# 3yp_node.net
KiCad netlist of a schematic drawn in EAGLE
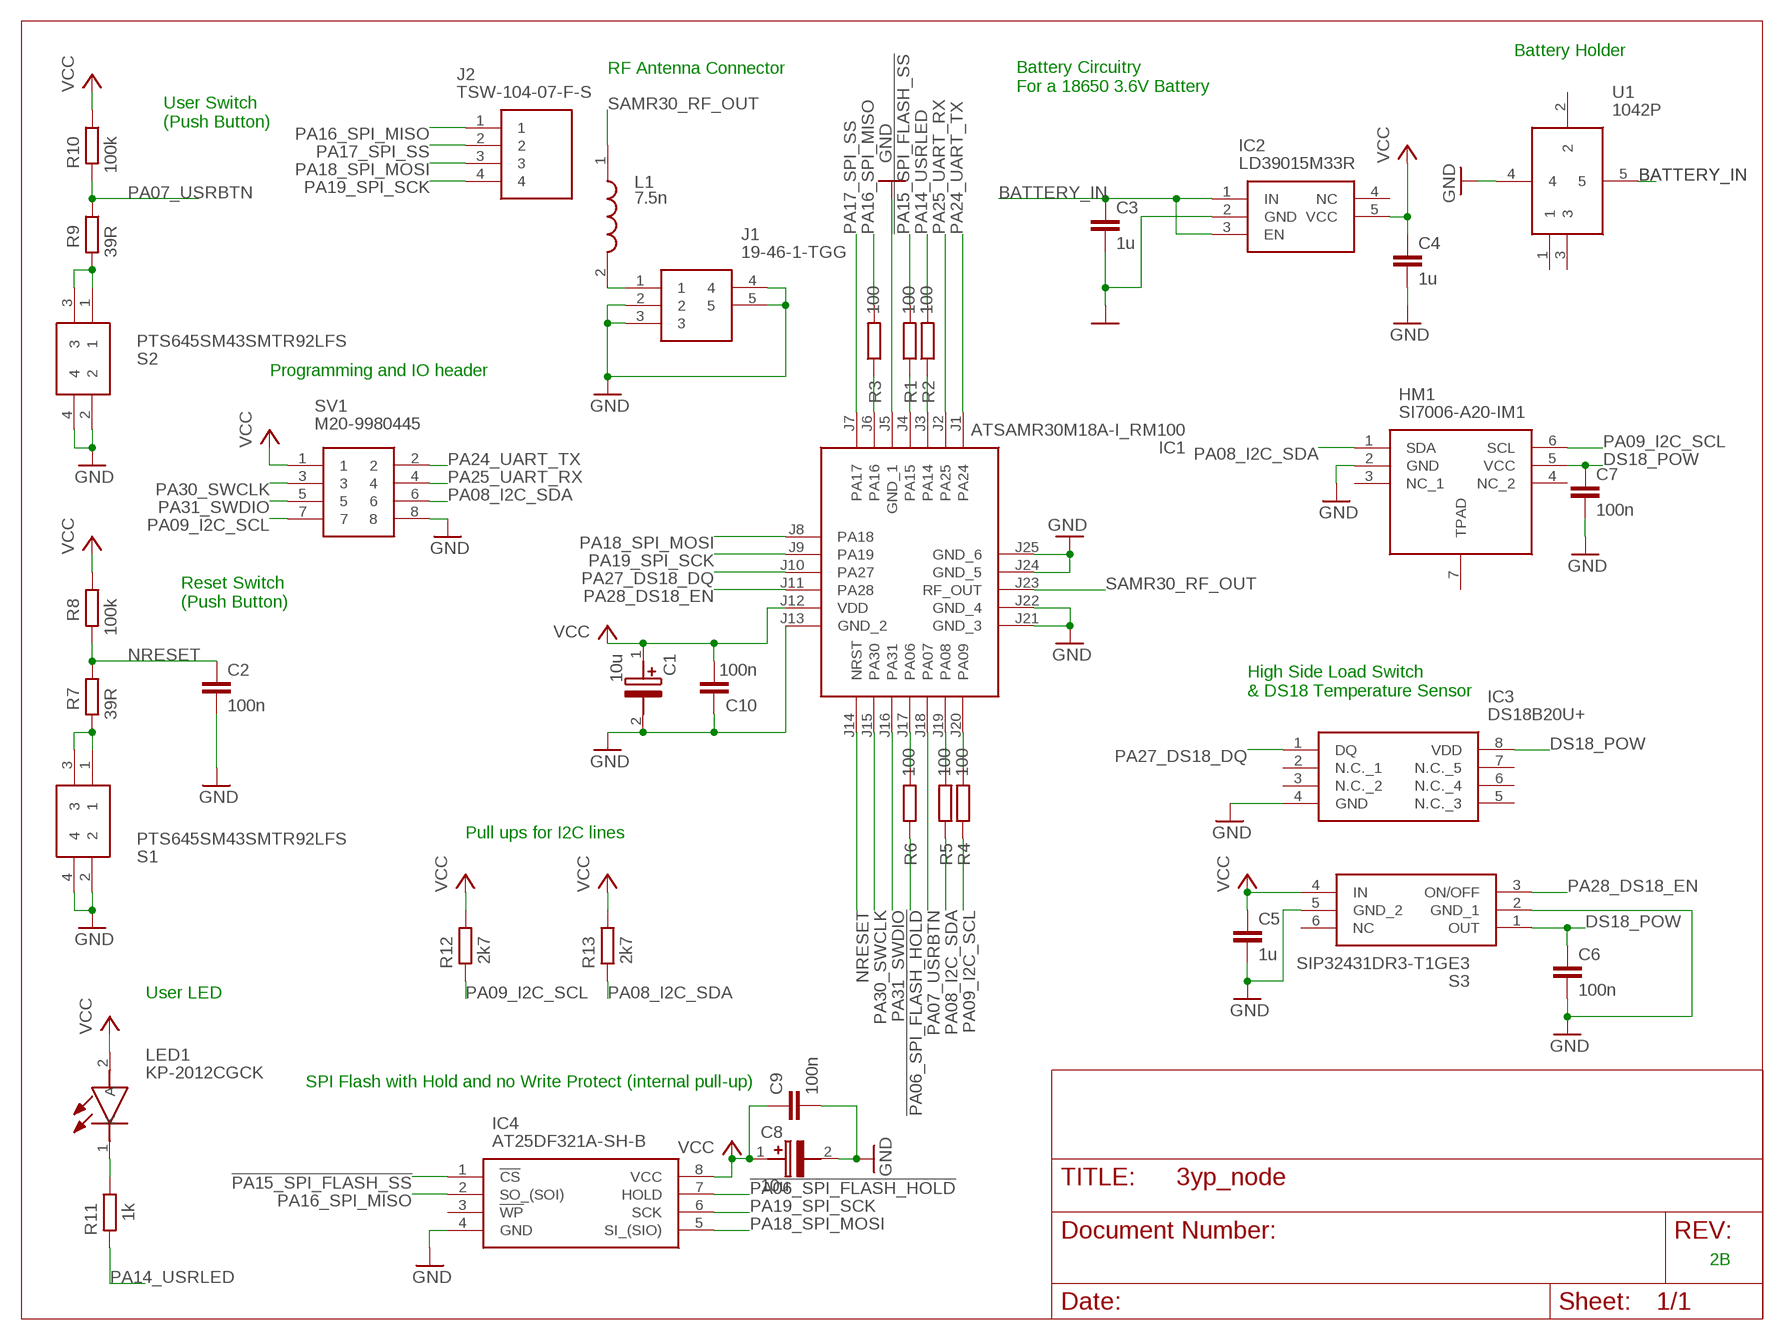
[diagram p0: schematic, sheet 1]

(export (version "E")
  (design (tool "Eeschema 10.0.6"))
  (components
    (comp (ref "C1")
      (value "10u")
      (footprint "eagle-import:CAPPM2014X170N")
      (fields
        (field (name "MANUFACTURER_PART_NUMBER") "TAJP106K006RNJ")
        (field (name "MOUSER_PART_NUMBER") "581-TAJP106K006RNJ")
      )
      (libsource (lib "eagle-import") (part "TAJP106K006RNJ"))
    )
    (comp (ref "C2")
      (value "100n")
      (footprint "eagle-import:C0805")
      (libsource (lib "eagle-import") (part "C-EUC0805"))
    )
    (comp (ref "C3")
      (value "1u")
      (footprint "eagle-import:C0805")
      (libsource (lib "eagle-import") (part "C-EUC0805"))
    )
    (comp (ref "C4")
      (value "1u")
      (footprint "eagle-import:C0805")
      (libsource (lib "eagle-import") (part "C-EUC0805"))
    )
    (comp (ref "C5")
      (value "1u")
      (footprint "eagle-import:C0805")
      (libsource (lib "eagle-import") (part "C-EUC0805"))
    )
    (comp (ref "C6")
      (value "100n")
      (footprint "eagle-import:C0805")
      (libsource (lib "eagle-import") (part "C-EUC0805"))
    )
    (comp (ref "C7")
      (value "100n")
      (footprint "eagle-import:C0805")
      (libsource (lib "eagle-import") (part "C-EUC0805"))
    )
    (comp (ref "C8")
      (value "10u")
      (footprint "eagle-import:CAPPM2014X170N")
      (fields
        (field (name "MANUFACTURER_PART_NUMBER") "TAJP106K006RNJ")
        (field (name "MOUSER_PART_NUMBER") "581-TAJP106K006RNJ")
      )
      (libsource (lib "eagle-import") (part "TAJP106K006RNJ"))
    )
    (comp (ref "C9")
      (value "100n")
      (footprint "eagle-import:C0805")
      (libsource (lib "eagle-import") (part "C-EUC0805"))
    )
    (comp (ref "C10")
      (value "100n")
      (footprint "eagle-import:C0805")
      (libsource (lib "eagle-import") (part "C-EUC0805"))
    )
    (comp (ref "HM1")
      (value "SI7006-A20-IM1")
      (footprint "eagle-import:SON100P300X300X80-7N")
      (fields
        (field (name "MANUFACTURER_PART_NUMBER") "Si7006-A20-IM1")
        (field (name "MOUSER_PART_NUMBER") "634-SI7006-A20-IM1")
        (field (name "RS_PART_NUMBER") "8652283P")
      )
      (libsource (lib "eagle-import") (part "SI7006-A20-IM1"))
    )
    (comp (ref "IC1")
      (value "ATSAMR30M18A-I_RM100")
      (footprint "eagle-import:ATSAMR30M18AIRM100")
      (fields
        (field (name "MANUFACTURER_PART_NUMBER") "ATSAMR30M18A-I/RM100")
        (field (name "MOUSER_PART_NUMBER") "556-AMR30M18AIRM100")
        (field (name "RS_PART_NUMBER") "1840450")
      )
      (libsource (lib "eagle-import") (part "ATSAMR30M18A-I_RM100"))
    )
    (comp (ref "IC2")
      (value "LD39015M33R")
      (footprint "eagle-import:SOT95P280X145-5N")
      (fields
        (field (name "MOUSER_PART_NUMBER") "511-LD39015M33R")
        (field (name "RS_PART_NUMBER") "7958965P")
      )
      (libsource (lib "eagle-import") (part "LD39015M33R"))
    )
    (comp (ref "IC3")
      (value "DS18B20U+")
      (footprint "eagle-import:SOP65P490X110-8N")
      (fields (field (name "MOUSER_PART_NUMBER") "700-DS18B20U"))
      (libsource (lib "eagle-import") (part "DS18B20U+"))
    )
    (comp (ref "IC4")
      (value "AT25DF321A-SH-B")
      (footprint "eagle-import:SOIC127P798X216-8N")
      (fields (field (name "MOUSER_PART_NUMBER") "556-AT25DF321A-SH-B"))
      (libsource (lib "eagle-import") (part "AT25DF321A-SH-B"))
    )
    (comp (ref "J1")
      (value "19-46-1-TGG")
      (footprint "eagle-import:19-46-1-TGG_1")
      (libsource (lib "eagle-import") (part "19-46-1-TGG"))
    )
    (comp (ref "J2")
      (value "TSW-104-07-F-S")
      (footprint "eagle-import:HDRV4W64P254_1X4_1016X241X838P")
      (fields (field (name "MOUSER_PART_NUMBER") "200-TSW10407FS") (field (name "RS_PART_NUMBER") "1612530"))
      (libsource (lib "eagle-import") (part "TSW-104-07-F-S"))
    )
    (comp (ref "L1")
      (value "7.5n")
      (footprint "eagle-import:INDC1006X60N")
      (fields
        (field (name "MANUFACTURER_PART_NUMBER") "MHQ1005P10NJT")
        (field (name "MOUSER_PART_NUMBER") "810-MHQ1005P10NJT")
        (field (name "RS_PART_NUMBER") "7958243P")
      )
      (libsource (lib "eagle-import") (part "MHQ1005P10NJT"))
    )
    (comp (ref "LED1")
      (value "KP-2012CGCK")
      (footprint "eagle-import:LEDC2012X110N")
      (fields (field (name "RS_PART_NUMBER") "8610037P"))
      (libsource (lib "eagle-import") (part "KP-2012CGCK"))
    )
    (comp (ref "R1")
      (value "100")
      (footprint "eagle-import:R0603")
      (libsource (lib "eagle-import") (part "R-EU_R0603"))
    )
    (comp (ref "R2")
      (value "100")
      (footprint "eagle-import:R0603")
      (libsource (lib "eagle-import") (part "R-EU_R0603"))
    )
    (comp (ref "R3")
      (value "100")
      (footprint "eagle-import:R0603")
      (libsource (lib "eagle-import") (part "R-EU_R0603"))
    )
    (comp (ref "R4")
      (value "100")
      (footprint "eagle-import:R0603")
      (libsource (lib "eagle-import") (part "R-EU_R0603"))
    )
    (comp (ref "R5")
      (value "100")
      (footprint "eagle-import:R0603")
      (libsource (lib "eagle-import") (part "R-EU_R0603"))
    )
    (comp (ref "R6")
      (value "100")
      (footprint "eagle-import:R0603")
      (libsource (lib "eagle-import") (part "R-EU_R0603"))
    )
    (comp (ref "R7")
      (value "39R")
      (footprint "eagle-import:R0603")
      (libsource (lib "eagle-import") (part "R-EU_R0603"))
    )
    (comp (ref "R8")
      (value "100k")
      (footprint "eagle-import:R0603")
      (libsource (lib "eagle-import") (part "R-EU_R0603"))
    )
    (comp (ref "R9")
      (value "39R")
      (footprint "eagle-import:R0603")
      (libsource (lib "eagle-import") (part "R-EU_R0603"))
    )
    (comp (ref "R10")
      (value "100k")
      (footprint "eagle-import:R0603")
      (libsource (lib "eagle-import") (part "R-EU_R0603"))
    )
    (comp (ref "R11")
      (value "1k")
      (footprint "eagle-import:R0603")
      (libsource (lib "eagle-import") (part "R-EU_R0603"))
    )
    (comp (ref "R12")
      (value "2k7")
      (footprint "eagle-import:R0603")
      (libsource (lib "eagle-import") (part "R-EU_R0603"))
    )
    (comp (ref "R13")
      (value "2k7")
      (footprint "eagle-import:R0603")
      (libsource (lib "eagle-import") (part "R-EU_R0603"))
    )
    (comp (ref "S1")
      (value "PTS645SM43SMTR92LFS")
      (footprint "eagle-import:PTS645(SMT)")
      (fields (field (name "MOUSER_PART_NUMBER") "611-PTS645SM43SMTR92"))
      (libsource (lib "eagle-import") (part "PTS645SM43SMTR92LFS"))
    )
    (comp (ref "S2")
      (value "PTS645SM43SMTR92LFS")
      (footprint "eagle-import:PTS645(SMT)")
      (fields (field (name "MOUSER_PART_NUMBER") "611-PTS645SM43SMTR92"))
      (libsource (lib "eagle-import") (part "PTS645SM43SMTR92LFS"))
    )
    (comp (ref "S3")
      (value "SIP32431DR3-T1GE3")
      (footprint "eagle-import:SOT65P210X110-6N")
      (fields
        (field (name "MOUSER_PART_NUMBER") "781-SIP32431DR3-GE3")
        (field (name "RS_PART_NUMBER") "1807353")
      )
      (libsource (lib "eagle-import") (part "SIP32431DR3-T1GE3"))
    )
    (comp (ref "SV1")
      (value "M20-9980445")
      (footprint "eagle-import:HDRV8W64P254_2X4_1016X508X868P")
      (fields
        (field (name "MOUSER_PART_NUMBER") "855-M20-9980445")
        (field (name "RS_PART_NUMBER") "6812941P")
      )
      (libsource (lib "eagle-import") (part "M20-9980445"))
    )
    (comp (ref "U1")
      (value "1042P")
      (footprint "eagle-import:1042P")
      (fields (field (name "MOUSER_PART_NUMBER") "534-1042P"))
      (libsource (lib "eagle-import") (part "1042P"))
    )
  )
  (nets
    (net (code "1") (name "/BATTERY_IN") (class "Default")
      (node (ref "C3") (pin "1") (pinfunction "1_1") (pintype "passive"))
      (node (ref "IC2") (pin "1") (pinfunction "IN_1") (pintype "input"))
      (node (ref "IC2") (pin "3") (pinfunction "EN_3") (pintype "bidirectional"))
      (node (ref "U1") (pin "5") (pinfunction "5_5") (pintype "bidirectional"))
    )
    (net (code "2") (name "/DS18_POW") (class "Default")
      (node (ref "C6") (pin "1") (pinfunction "1_1") (pintype "passive"))
      (node (ref "C7") (pin "1") (pinfunction "1_1") (pintype "passive"))
      (node (ref "HM1") (pin "5") (pinfunction "VCC_5") (pintype "power_in"))
      (node (ref "IC3") (pin "8") (pinfunction "VDD_8") (pintype "power_in"))
      (node (ref "S3") (pin "1") (pinfunction "OUT_1") (pintype "power_in"))
    )
    (net (code "3") (name "/NRESET") (class "Default")
      (node (ref "C2") (pin "1") (pinfunction "1_1") (pintype "passive"))
      (node (ref "IC1") (pin "J14") (pinfunction "NRST_J14") (pintype "bidirectional"))
      (node (ref "R7") (pin "1") (pinfunction "1_1") (pintype "passive"))
      (node (ref "R8") (pin "2") (pinfunction "2_2") (pintype "passive"))
    )
    (net (code "4") (name "/PA07_USRBTN") (class "Default")
      (node (ref "IC1") (pin "J18") (pinfunction "PA07_J18") (pintype "bidirectional"))
      (node (ref "R10") (pin "2") (pinfunction "2_2") (pintype "passive"))
      (node (ref "R9") (pin "1") (pinfunction "1_1") (pintype "passive"))
    )
    (net (code "5") (name "/PA08_I2C_SDA") (class "Default")
      (node (ref "HM1") (pin "1") (pinfunction "SDA_1") (pintype "bidirectional"))
      (node (ref "R13") (pin "2") (pinfunction "2_2") (pintype "passive"))
      (node (ref "R5") (pin "1") (pinfunction "1_1") (pintype "passive"))
      (node (ref "SV1") (pin "6") (pinfunction "6_6") (pintype "bidirectional"))
    )
    (net (code "6") (name "/PA09_I2C_SCL") (class "Default")
      (node (ref "HM1") (pin "6") (pinfunction "SCL_6") (pintype "input"))
      (node (ref "R12") (pin "2") (pinfunction "2_2") (pintype "passive"))
      (node (ref "R4") (pin "1") (pinfunction "1_1") (pintype "passive"))
      (node (ref "SV1") (pin "7") (pinfunction "7_7") (pintype "bidirectional"))
    )
    (net (code "7") (name "/PA14_USRLED") (class "Default")
      (node (ref "R11") (pin "2") (pinfunction "2_2") (pintype "passive"))
      (node (ref "R2") (pin "2") (pinfunction "2_2") (pintype "passive"))
    )
    (net (code "8") (name "/PA16_SPI_MISO") (class "Default")
      (node (ref "IC4") (pin "2") (pinfunction "SO_(SOI)_2") (pintype "bidirectional"))
      (node (ref "J2") (pin "1") (pinfunction "1_1") (pintype "bidirectional"))
      (node (ref "R3") (pin "2") (pinfunction "2_2") (pintype "passive"))
    )
    (net (code "9") (name "/PA17_SPI_SS") (class "Default")
      (node (ref "IC1") (pin "J7") (pinfunction "PA17_J7") (pintype "bidirectional"))
      (node (ref "J2") (pin "2") (pinfunction "2_2") (pintype "bidirectional"))
    )
    (net (code "10") (name "/PA18_SPI_MOSI") (class "Default")
      (node (ref "IC1") (pin "J8") (pinfunction "PA18_J8") (pintype "bidirectional"))
      (node (ref "IC4") (pin "5") (pinfunction "SI_(SIO)_5") (pintype "bidirectional"))
      (node (ref "J2") (pin "3") (pinfunction "3_3") (pintype "bidirectional"))
    )
    (net (code "11") (name "/PA19_SPI_SCK") (class "Default")
      (node (ref "IC1") (pin "J9") (pinfunction "PA19_J9") (pintype "bidirectional"))
      (node (ref "IC4") (pin "6") (pinfunction "SCK_6") (pintype "bidirectional"))
      (node (ref "J2") (pin "4") (pinfunction "4_4") (pintype "bidirectional"))
    )
    (net (code "12") (name "/PA24_UART_TX") (class "Default")
      (node (ref "IC1") (pin "J1") (pinfunction "PA24_J1") (pintype "bidirectional"))
      (node (ref "SV1") (pin "2") (pinfunction "2_2") (pintype "bidirectional"))
    )
    (net (code "13") (name "/PA25_UART_RX") (class "Default")
      (node (ref "IC1") (pin "J2") (pinfunction "PA25_J2") (pintype "bidirectional"))
      (node (ref "SV1") (pin "4") (pinfunction "4_4") (pintype "bidirectional"))
    )
    (net (code "14") (name "/PA27_DS18_DQ") (class "Default")
      (node (ref "IC1") (pin "J10") (pinfunction "PA27_J10") (pintype "bidirectional"))
      (node (ref "IC3") (pin "1") (pinfunction "DQ_1") (pintype "bidirectional"))
    )
    (net (code "15") (name "/PA28_DS18_EN") (class "Default")
      (node (ref "IC1") (pin "J11") (pinfunction "PA28_J11") (pintype "bidirectional"))
      (node (ref "S3") (pin "3") (pinfunction "ON/OFF_3") (pintype "bidirectional"))
    )
    (net (code "16") (name "/PA30_SWCLK") (class "Default")
      (node (ref "IC1") (pin "J15") (pinfunction "PA30_J15") (pintype "bidirectional"))
      (node (ref "SV1") (pin "3") (pinfunction "3_3") (pintype "bidirectional"))
    )
    (net (code "17") (name "/PA31_SWDIO") (class "Default")
      (node (ref "IC1") (pin "J16") (pinfunction "PA31_J16") (pintype "bidirectional"))
      (node (ref "SV1") (pin "5") (pinfunction "5_5") (pintype "bidirectional"))
    )
    (net (code "18") (name "/SAMR30_RF_OUT") (class "Default")
      (node (ref "IC1") (pin "J23") (pinfunction "RF_OUT_J23") (pintype "bidirectional"))
      (node (ref "L1") (pin "1") (pinfunction "1_1") (pintype "bidirectional"))
    )
    (net (code "19") (name "/~{PA06_SPI_FLASH_HOLD}") (class "Default")
      (node (ref "IC4") (pin "7") (pinfunction "HOLD_7") (pintype "bidirectional"))
      (node (ref "R6") (pin "1") (pinfunction "1_1") (pintype "passive"))
    )
    (net (code "20") (name "/~{PA15_SPI_FLASH_SS}") (class "Default")
      (node (ref "IC4") (pin "1") (pinfunction "~{CS}_1") (pintype "input"))
      (node (ref "R1") (pin "2") (pinfunction "2_2") (pintype "passive"))
    )
    (net (code "21") (name "GND") (class "Default")
      (node (ref "C1") (pin "2") (pinfunction "-_2") (pintype "bidirectional"))
      (node (ref "C10") (pin "1") (pinfunction "1_1") (pintype "passive"))
      (node (ref "C2") (pin "2") (pinfunction "2_2") (pintype "passive"))
      (node (ref "C3") (pin "2") (pinfunction "2_2") (pintype "passive"))
      (node (ref "C4") (pin "2") (pinfunction "2_2") (pintype "passive"))
      (node (ref "C5") (pin "2") (pinfunction "2_2") (pintype "passive"))
      (node (ref "C6") (pin "2") (pinfunction "2_2") (pintype "passive"))
      (node (ref "C7") (pin "2") (pinfunction "2_2") (pintype "passive"))
      (node (ref "C8") (pin "2") (pinfunction "-_2") (pintype "bidirectional"))
      (node (ref "C9") (pin "2") (pinfunction "2_2") (pintype "passive"))
      (node (ref "HM1") (pin "2") (pinfunction "GND_2") (pintype "power_in"))
      (node (ref "IC1") (pin "J13") (pinfunction "GND_2_J13") (pintype "bidirectional"))
      (node (ref "IC1") (pin "J21") (pinfunction "GND_3_J21") (pintype "bidirectional"))
      (node (ref "IC1") (pin "J22") (pinfunction "GND_4_J22") (pintype "bidirectional"))
      (node (ref "IC1") (pin "J24") (pinfunction "GND_5_J24") (pintype "bidirectional"))
      (node (ref "IC1") (pin "J25") (pinfunction "GND_6_J25") (pintype "bidirectional"))
      (node (ref "IC1") (pin "J5") (pinfunction "GND_1_J5") (pintype "bidirectional"))
      (node (ref "IC2") (pin "2") (pinfunction "GND_2") (pintype "power_in"))
      (node (ref "IC3") (pin "4") (pinfunction "GND_4") (pintype "power_in"))
      (node (ref "IC4") (pin "4") (pinfunction "GND_4") (pintype "power_in"))
      (node (ref "J1") (pin "2") (pinfunction "2_2") (pintype "bidirectional"))
      (node (ref "J1") (pin "3") (pinfunction "3_3") (pintype "bidirectional"))
      (node (ref "J1") (pin "4") (pinfunction "4_4") (pintype "bidirectional"))
      (node (ref "J1") (pin "5") (pinfunction "5_5") (pintype "bidirectional"))
      (node (ref "S1") (pin "2") (pinfunction "2_2") (pintype "bidirectional"))
      (node (ref "S1") (pin "4") (pinfunction "4_4") (pintype "bidirectional"))
      (node (ref "S2") (pin "2") (pinfunction "2_2") (pintype "bidirectional"))
      (node (ref "S2") (pin "4") (pinfunction "4_4") (pintype "bidirectional"))
      (node (ref "S3") (pin "2") (pinfunction "GND_1_2") (pintype "bidirectional"))
      (node (ref "S3") (pin "5") (pinfunction "GND_2_5") (pintype "bidirectional"))
      (node (ref "SV1") (pin "8") (pinfunction "8_8") (pintype "bidirectional"))
      (node (ref "U1") (pin "4") (pinfunction "4_4") (pintype "bidirectional"))
    )
    (net (code "22") (name "Net-(IC1-PA06)") (class "Default")
      (node (ref "IC1") (pin "J17") (pinfunction "PA06_J17") (pintype "bidirectional"))
      (node (ref "R6") (pin "2") (pinfunction "2_2") (pintype "passive"))
    )
    (net (code "23") (name "Net-(IC1-PA08)") (class "Default")
      (node (ref "IC1") (pin "J19") (pinfunction "PA08_J19") (pintype "bidirectional"))
      (node (ref "R5") (pin "2") (pinfunction "2_2") (pintype "passive"))
    )
    (net (code "24") (name "Net-(IC1-PA09)") (class "Default")
      (node (ref "IC1") (pin "J20") (pinfunction "PA09_J20") (pintype "bidirectional"))
      (node (ref "R4") (pin "2") (pinfunction "2_2") (pintype "passive"))
    )
    (net (code "25") (name "Net-(IC1-PA14)") (class "Default")
      (node (ref "IC1") (pin "J3") (pinfunction "PA14_J3") (pintype "bidirectional"))
      (node (ref "R2") (pin "1") (pinfunction "1_1") (pintype "passive"))
    )
    (net (code "26") (name "Net-(IC1-PA15)") (class "Default")
      (node (ref "IC1") (pin "J4") (pinfunction "PA15_J4") (pintype "bidirectional"))
      (node (ref "R1") (pin "1") (pinfunction "1_1") (pintype "passive"))
    )
    (net (code "27") (name "Net-(IC1-PA16)") (class "Default")
      (node (ref "IC1") (pin "J6") (pinfunction "PA16_J6") (pintype "bidirectional"))
      (node (ref "R3") (pin "1") (pinfunction "1_1") (pintype "passive"))
    )
    (net (code "28") (name "Net-(J1-Pad1)") (class "Default")
      (node (ref "J1") (pin "1") (pinfunction "1_1") (pintype "bidirectional"))
      (node (ref "L1") (pin "2") (pinfunction "2_2") (pintype "bidirectional"))
    )
    (net (code "29") (name "Net-(LED1-K)") (class "Default")
      (node (ref "LED1") (pin "1") (pinfunction "K_1") (pintype "bidirectional"))
      (node (ref "R11") (pin "1") (pinfunction "1_1") (pintype "passive"))
    )
    (net (code "30") (name "Net-(R7-Pad2)") (class "Default")
      (node (ref "R7") (pin "2") (pinfunction "2_2") (pintype "passive"))
      (node (ref "S1") (pin "1") (pinfunction "1_1") (pintype "bidirectional"))
      (node (ref "S1") (pin "3") (pinfunction "3_3") (pintype "bidirectional"))
    )
    (net (code "31") (name "Net-(R9-Pad2)") (class "Default")
      (node (ref "R9") (pin "2") (pinfunction "2_2") (pintype "passive"))
      (node (ref "S2") (pin "1") (pinfunction "1_1") (pintype "bidirectional"))
      (node (ref "S2") (pin "3") (pinfunction "3_3") (pintype "bidirectional"))
    )
    (net (code "32") (name "VCC") (class "Default")
      (node (ref "C1") (pin "1") (pinfunction "+_1") (pintype "bidirectional"))
      (node (ref "C10") (pin "2") (pinfunction "2_2") (pintype "passive"))
      (node (ref "C4") (pin "1") (pinfunction "1_1") (pintype "passive"))
      (node (ref "C5") (pin "1") (pinfunction "1_1") (pintype "passive"))
      (node (ref "C8") (pin "1") (pinfunction "+_1") (pintype "bidirectional"))
      (node (ref "C9") (pin "1") (pinfunction "1_1") (pintype "passive"))
      (node (ref "IC1") (pin "J12") (pinfunction "VDD_J12") (pintype "bidirectional"))
      (node (ref "IC2") (pin "5") (pinfunction "VCC_5") (pintype "power_in"))
      (node (ref "IC4") (pin "8") (pinfunction "VCC_8") (pintype "power_in"))
      (node (ref "LED1") (pin "2") (pinfunction "A_2") (pintype "bidirectional"))
      (node (ref "R10") (pin "1") (pinfunction "1_1") (pintype "passive"))
      (node (ref "R12") (pin "1") (pinfunction "1_1") (pintype "passive"))
      (node (ref "R13") (pin "1") (pinfunction "1_1") (pintype "passive"))
      (node (ref "R8") (pin "1") (pinfunction "1_1") (pintype "passive"))
      (node (ref "S3") (pin "4") (pinfunction "IN_4") (pintype "bidirectional"))
      (node (ref "SV1") (pin "1") (pinfunction "1_1") (pintype "bidirectional"))
    )
    (net (code "33") (name "unconnected-(HM1-NC_1-Pad3)") (class "Default")
      (node (ref "HM1") (pin "3") (pinfunction "NC_1_3") (pintype "bidirectional"))
    )
    (net (code "34") (name "unconnected-(HM1-NC_2-Pad4)") (class "Default")
      (node (ref "HM1") (pin "4") (pinfunction "NC_2_4") (pintype "bidirectional"))
    )
    (net (code "35") (name "unconnected-(HM1-TPAD-Pad7)") (class "Default")
      (node (ref "HM1") (pin "7") (pinfunction "TPAD_7") (pintype "bidirectional"))
    )
    (net (code "36") (name "unconnected-(IC2-NC-Pad4)") (class "Default")
      (node (ref "IC2") (pin "4") (pinfunction "NC_4") (pintype "no_connect"))
    )
    (net (code "37") (name "unconnected-(IC3-N.C._1-Pad2)") (class "Default")
      (node (ref "IC3") (pin "2") (pinfunction "N.C._1_2") (pintype "bidirectional"))
    )
    (net (code "38") (name "unconnected-(IC3-N.C._2-Pad3)") (class "Default")
      (node (ref "IC3") (pin "3") (pinfunction "N.C._2_3") (pintype "bidirectional"))
    )
    (net (code "39") (name "unconnected-(IC3-N.C._3-Pad5)") (class "Default")
      (node (ref "IC3") (pin "5") (pinfunction "N.C._3_5") (pintype "bidirectional"))
    )
    (net (code "40") (name "unconnected-(IC3-N.C._4-Pad6)") (class "Default")
      (node (ref "IC3") (pin "6") (pinfunction "N.C._4_6") (pintype "bidirectional"))
    )
    (net (code "41") (name "unconnected-(IC3-N.C._5-Pad7)") (class "Default")
      (node (ref "IC3") (pin "7") (pinfunction "N.C._5_7") (pintype "bidirectional"))
    )
    (net (code "42") (name "unconnected-(IC4-~{WP}-Pad3)") (class "Default")
      (node (ref "IC4") (pin "3") (pinfunction "~{WP}_3") (pintype "bidirectional"))
    )
    (net (code "43") (name "unconnected-(S3-NC-Pad6)") (class "Default")
      (node (ref "S3") (pin "6") (pinfunction "NC_6") (pintype "no_connect"))
    )
    (net (code "44") (name "unconnected-(U1-Pad1)") (class "Default")
      (node (ref "U1") (pin "1") (pinfunction "1_1") (pintype "bidirectional"))
    )
    (net (code "45") (name "unconnected-(U1-Pad2)") (class "Default")
      (node (ref "U1") (pin "2") (pinfunction "2_2") (pintype "bidirectional"))
    )
    (net (code "46") (name "unconnected-(U1-Pad3)") (class "Default")
      (node (ref "U1") (pin "3") (pinfunction "3_3") (pintype "bidirectional"))
    )
  )
)
